# RF.net
KiCad netlist of a schematic drawn in Altium Designer
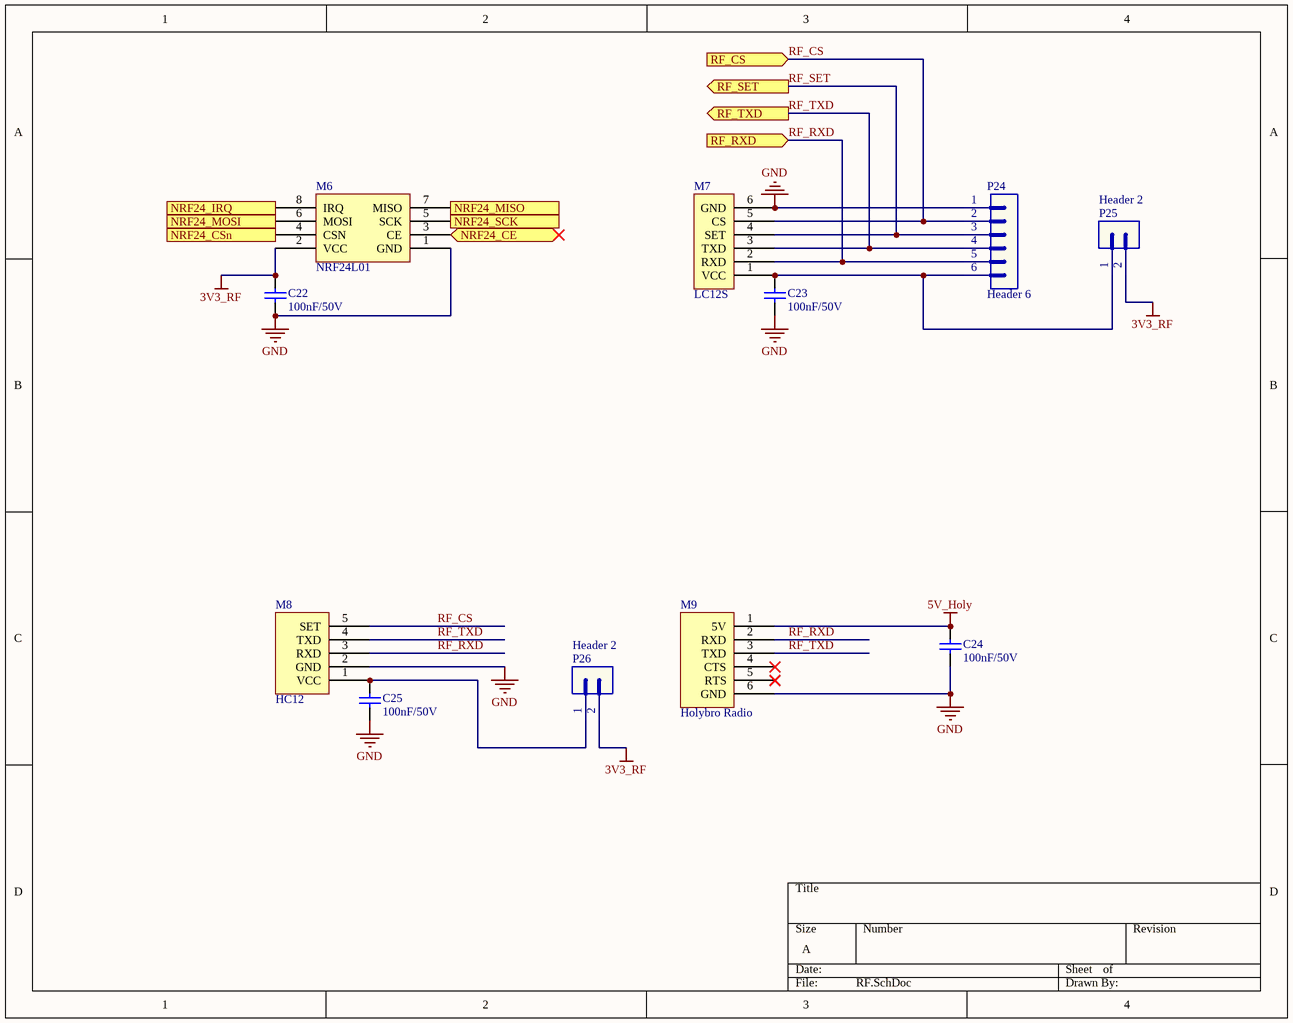
[diagram p0: RF.SchDoc]

(export (version "E")
  (design (tool "Eeschema 10.0.6"))
  (components
    (comp (ref "C22")
      (value "100nF/50V")
      (footprint "CAP-SM-0805")
      (description "CAP CER 0.1UF 50V Y5V 0805")
      (fields
        (field (name "MANUFACTURER") "Samsung Electro-Mechanics")
        (field (name "MANUFACTURER PART NUMBER") "CL21F104ZBCNNNC")
      )
      (libsource (lib "Capacitor") (part "Cap-100nF-50V-0805"))
    )
    (comp (ref "C23")
      (value "100nF/50V")
      (footprint "CAP-SM-0805")
      (description "CAP CER 0.1UF 50V Y5V 0805")
      (fields
        (field (name "MANUFACTURER") "Samsung Electro-Mechanics")
        (field (name "MANUFACTURER PART NUMBER") "CL21F104ZBCNNNC")
      )
      (libsource (lib "Capacitor") (part "Cap-100nF-50V-0805"))
    )
    (comp (ref "C24")
      (value "100nF/50V")
      (footprint "CAP-SM-0805")
      (description "CAP CER 0.1UF 50V Y5V 0805")
      (fields
        (field (name "MANUFACTURER") "Samsung Electro-Mechanics")
        (field (name "MANUFACTURER PART NUMBER") "CL21F104ZBCNNNC")
      )
      (libsource (lib "Capacitor") (part "Cap-100nF-50V-0805"))
    )
    (comp (ref "C25")
      (value "100nF/50V")
      (footprint "CAP-SM-0805")
      (description "CAP CER 0.1UF 50V Y5V 0805")
      (fields
        (field (name "MANUFACTURER") "Samsung Electro-Mechanics")
        (field (name "MANUFACTURER PART NUMBER") "CL21F104ZBCNNNC")
      )
      (libsource (lib "Capacitor") (part "Cap-100nF-50V-0805"))
    )
    (comp (ref "M6")
      (value "NRF24L01")
      (footprint "NRF24L01")
      (fields (field (name "LOCAL SUPPLIER PART NUMBER") "HS000888"))
      (libsource (lib "PIFWRoBot") (part "NRF24L01"))
    )
    (comp (ref "M7")
      (value "LC12S")
      (footprint "LC12S")
      (fields (field (name "LOCAL SUPPLIER PART NUMBER") "HS000895"))
      (libsource (lib "PIFWRoBot") (part "LC12S"))
    )
    (comp (ref "M8")
      (value "HC12")
      (footprint "HC12")
      (fields (field (name "LOCAL SUPPLIER PART NUMBER") "HS000897"))
      (libsource (lib "PIFWRoBot") (part "HC12"))
    )
    (comp (ref "M9")
      (value "Holybro Radio")
      (footprint "HOLYBRO RADIO")
      (libsource (lib "PIFWRoBot") (part "HOLYBRO RADIO"))
    )
    (comp (ref "P24")
      (value "Header 6")
      (footprint "JP6")
      (description "Header, 6-Pin")
      (fields (field (name "PUBLISHER") "Altium Limited"))
      (libsource (lib "Header-connector") (part "Header 6"))
    )
    (comp (ref "P25")
      (value "Header 2")
      (footprint "JP2")
      (description "Header, 2-Pin")
      (fields (field (name "PUBLISHER") "Altium Limited"))
      (libsource (lib "Header-connector") (part "Header 2"))
    )
    (comp (ref "P26")
      (value "Header 2")
      (footprint "JP2")
      (description "Header, 2-Pin")
      (fields (field (name "PUBLISHER") "Altium Limited"))
      (libsource (lib "Header-connector") (part "Header 2"))
    )
  )
  (nets
    (net (code "1") (name "/NRF24_CE") (class "Default")
      (node (ref "M6") (pin "3") (pinfunction "CE_3") (pintype "passive"))
    )
    (net (code "2") (name "/NRF24_CSn") (class "Default")
      (node (ref "M6") (pin "4") (pinfunction "CSN_4") (pintype "passive"))
    )
    (net (code "3") (name "/NRF24_IRQ") (class "Default")
      (node (ref "M6") (pin "8") (pinfunction "IRQ_8") (pintype "passive"))
    )
    (net (code "4") (name "/NRF24_MISO") (class "Default")
      (node (ref "M6") (pin "7") (pinfunction "MISO_7") (pintype "passive"))
    )
    (net (code "5") (name "/NRF24_MOSI") (class "Default")
      (node (ref "M6") (pin "6") (pinfunction "MOSI_6") (pintype "passive"))
    )
    (net (code "6") (name "/NRF24_SCK") (class "Default")
      (node (ref "M6") (pin "5") (pinfunction "SCK_5") (pintype "passive"))
    )
    (net (code "7") (name "/RF_CS") (class "Default")
      (node (ref "M7") (pin "5") (pinfunction "CS_5") (pintype "passive"))
      (node (ref "M8") (pin "5") (pinfunction "SET_5") (pintype "passive"))
      (node (ref "P24") (pin "2") (pinfunction "2_2") (pintype "passive"))
    )
    (net (code "8") (name "/RF_RXD") (class "Default")
      (node (ref "M7") (pin "2") (pinfunction "RXD_2") (pintype "passive"))
      (node (ref "M8") (pin "3") (pinfunction "RXD_3") (pintype "passive"))
      (node (ref "M9") (pin "2") (pinfunction "RXD_2") (pintype "passive"))
      (node (ref "P24") (pin "5") (pinfunction "5_5") (pintype "passive"))
    )
    (net (code "9") (name "/RF_SET") (class "Default")
      (node (ref "M7") (pin "4") (pinfunction "SET_4") (pintype "passive"))
      (node (ref "P24") (pin "3") (pinfunction "3_3") (pintype "passive"))
    )
    (net (code "10") (name "/RF_TXD") (class "Default")
      (node (ref "M7") (pin "3") (pinfunction "TXD_3") (pintype "passive"))
      (node (ref "M8") (pin "4") (pinfunction "TXD_4") (pintype "passive"))
      (node (ref "M9") (pin "3") (pinfunction "TXD_3") (pintype "passive"))
      (node (ref "P24") (pin "4") (pinfunction "4_4") (pintype "passive"))
    )
    (net (code "11") (name "3V3_RF") (class "Default")
      (node (ref "C22") (pin "2") (pinfunction "2_2") (pintype "passive"))
      (node (ref "M6") (pin "2") (pinfunction "VCC_2") (pintype "passive"))
      (node (ref "P25") (pin "2") (pinfunction "2_2") (pintype "passive"))
      (node (ref "P26") (pin "2") (pinfunction "2_2") (pintype "passive"))
    )
    (net (code "12") (name "5V_Holy") (class "Default")
      (node (ref "C24") (pin "2") (pinfunction "2_2") (pintype "passive"))
      (node (ref "M9") (pin "1") (pinfunction "5V_1") (pintype "passive"))
    )
    (net (code "13") (name "GND") (class "Default")
      (node (ref "C22") (pin "1") (pinfunction "1_1") (pintype "passive"))
      (node (ref "C23") (pin "1") (pinfunction "1_1") (pintype "passive"))
      (node (ref "C24") (pin "1") (pinfunction "1_1") (pintype "passive"))
      (node (ref "C25") (pin "1") (pinfunction "1_1") (pintype "passive"))
      (node (ref "M6") (pin "1") (pinfunction "GND_1") (pintype "passive"))
      (node (ref "M7") (pin "6") (pinfunction "GND_6") (pintype "passive"))
      (node (ref "M8") (pin "2") (pinfunction "GND_2") (pintype "passive"))
      (node (ref "M9") (pin "6") (pinfunction "GND_6") (pintype "passive"))
      (node (ref "P24") (pin "1") (pinfunction "1_1") (pintype "passive"))
    )
    (net (code "14") (name "Net-(M7-VCC)") (class "Default")
      (node (ref "C23") (pin "2") (pinfunction "2_2") (pintype "passive"))
      (node (ref "M7") (pin "1") (pinfunction "VCC_1") (pintype "passive"))
      (node (ref "P24") (pin "6") (pinfunction "6_6") (pintype "passive"))
      (node (ref "P25") (pin "1") (pinfunction "1_1") (pintype "passive"))
    )
    (net (code "15") (name "Net-(M8-VCC)") (class "Default")
      (node (ref "C25") (pin "2") (pinfunction "2_2") (pintype "passive"))
      (node (ref "M8") (pin "1") (pinfunction "VCC_1") (pintype "passive"))
      (node (ref "P26") (pin "1") (pinfunction "1_1") (pintype "passive"))
    )
    (net (code "16") (name "unconnected-(M9-CTS-Pad4)") (class "Default")
      (node (ref "M9") (pin "4") (pinfunction "CTS_4") (pintype "passive+no_connect"))
    )
    (net (code "17") (name "unconnected-(M9-RTS-Pad5)") (class "Default")
      (node (ref "M9") (pin "5") (pinfunction "RTS_5") (pintype "passive+no_connect"))
    )
  )
)
